# Power.net
KiCad netlist of a schematic drawn in Altium Designer
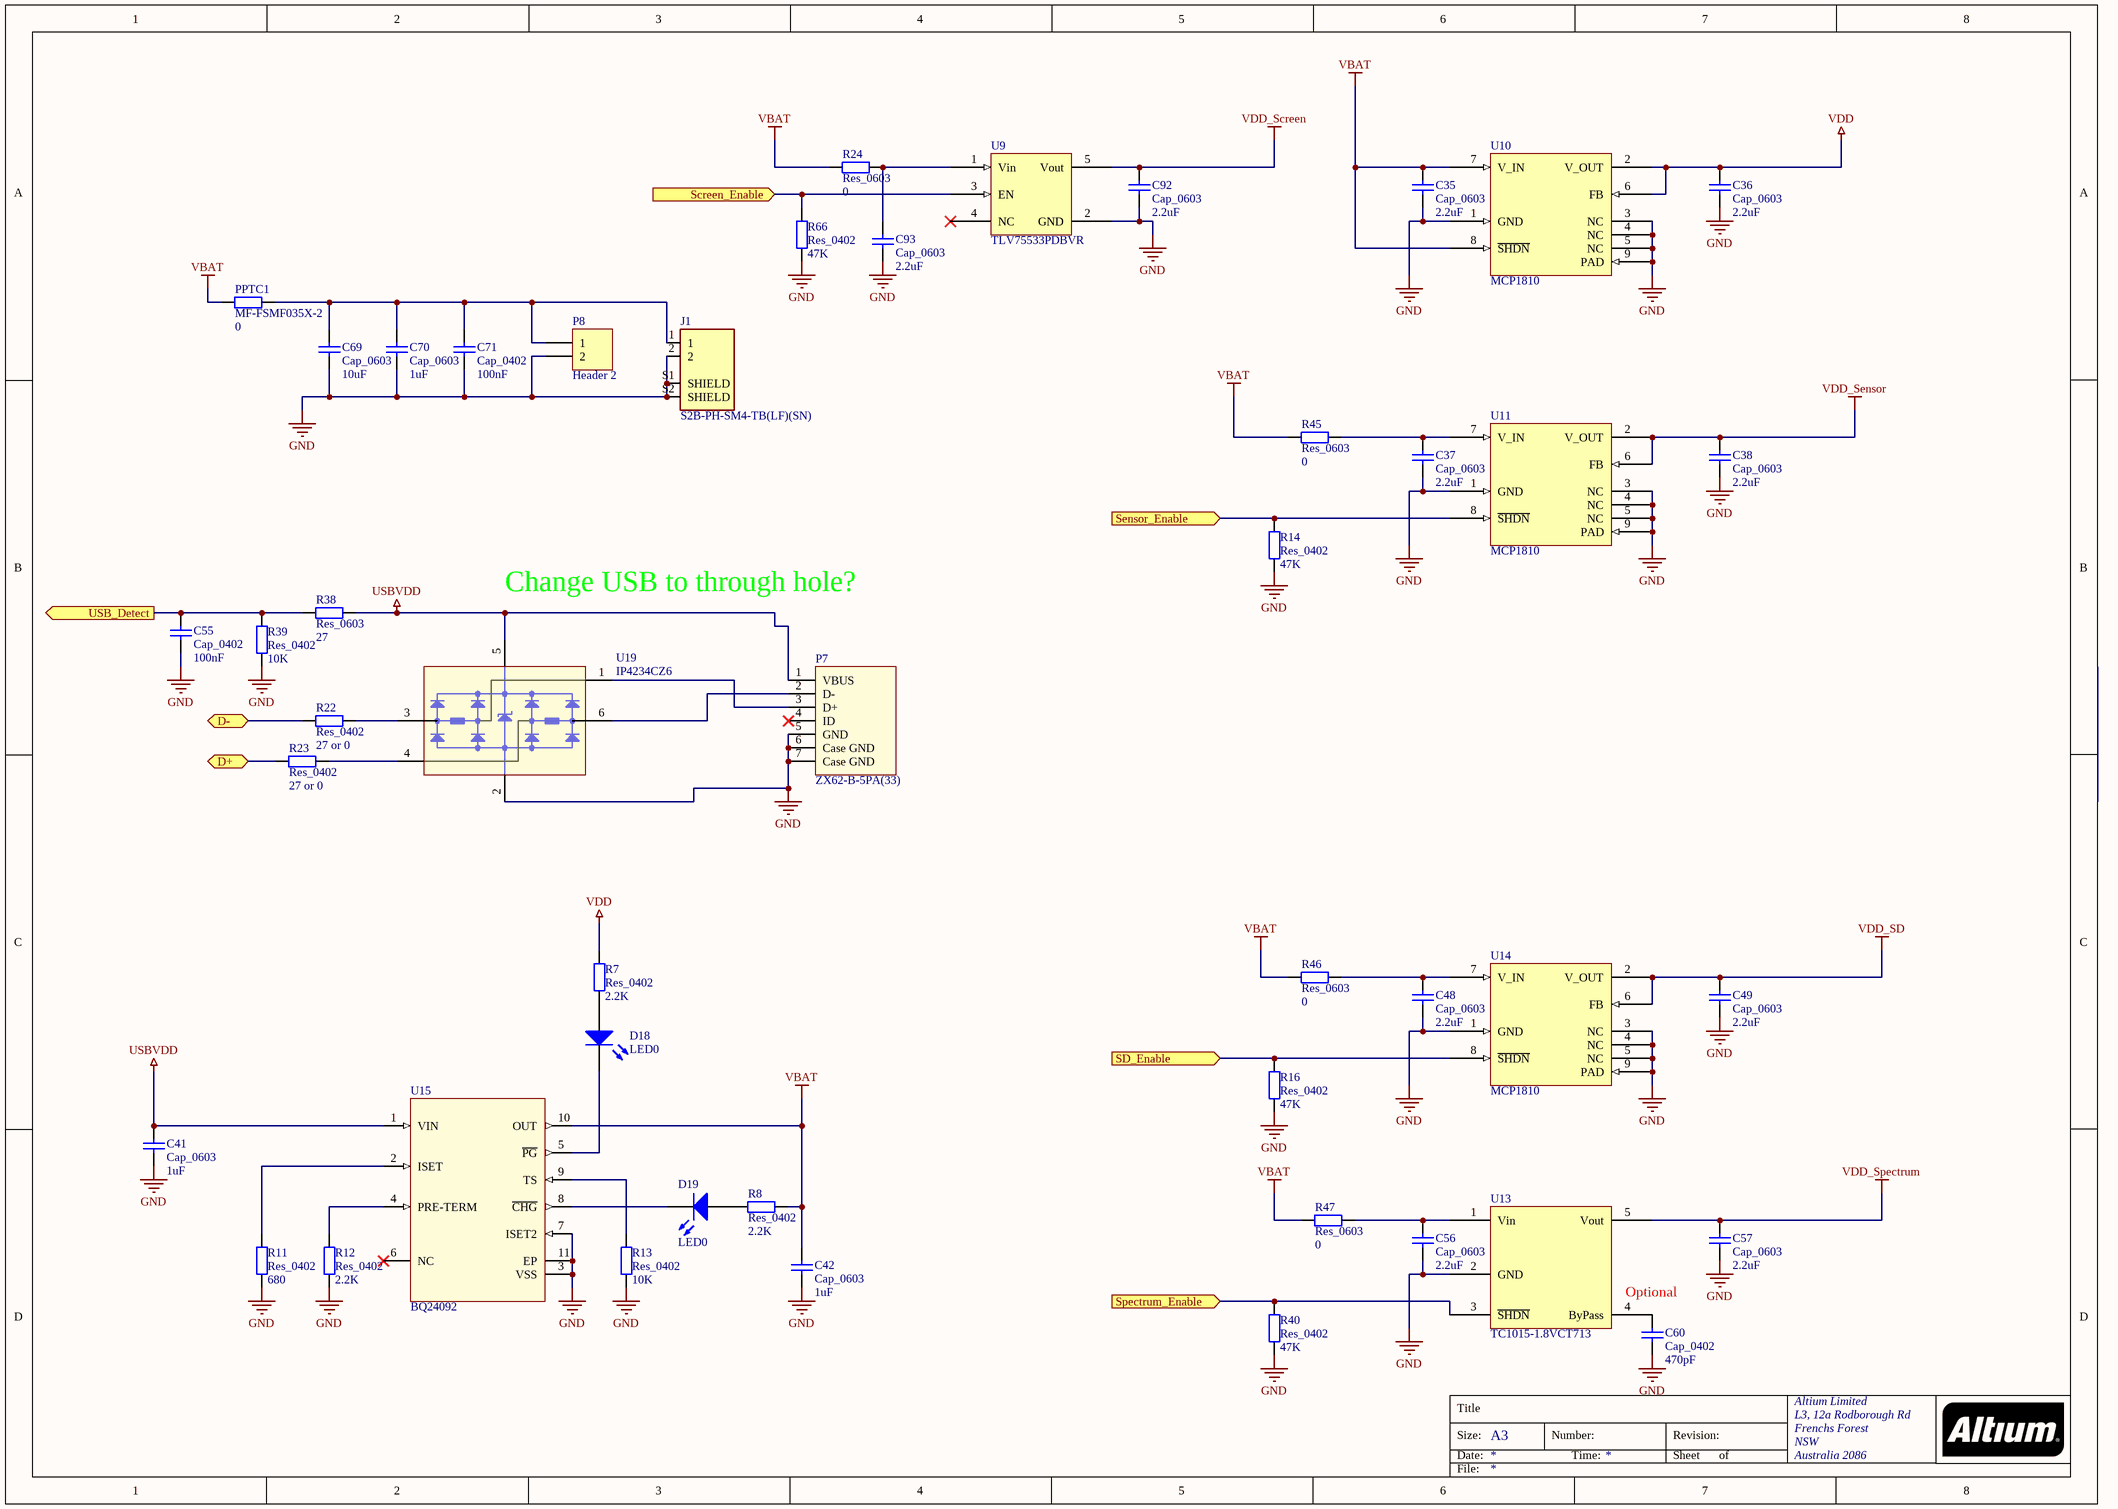
[diagram p0: Power.SchDoc]

(export (version "E")
  (design (tool "Eeschema 10.0.6"))
  (components
    (comp (ref "C35")
      (value "Cap_0603")
      (footprint "0603")
      (description "Capacitor")
      (fields (field (name "ALTIUM_VALUE") "2.2uF") (field (name "PUBLISHER") "Altium Limited"))
      (libsource (lib "Schematic_Components") (part "Cap_0603"))
    )
    (comp (ref "C36")
      (value "Cap_0603")
      (footprint "0603")
      (description "Capacitor")
      (fields (field (name "ALTIUM_VALUE") "2.2uF") (field (name "PUBLISHER") "Altium Limited"))
      (libsource (lib "Schematic_Components") (part "Cap_0603"))
    )
    (comp (ref "C37")
      (value "Cap_0603")
      (footprint "0603")
      (description "Capacitor")
      (fields (field (name "ALTIUM_VALUE") "2.2uF") (field (name "PUBLISHER") "Altium Limited"))
      (libsource (lib "Schematic_Components") (part "Cap_0603"))
    )
    (comp (ref "C38")
      (value "Cap_0603")
      (footprint "0603")
      (description "Capacitor")
      (fields (field (name "ALTIUM_VALUE") "2.2uF") (field (name "PUBLISHER") "Altium Limited"))
      (libsource (lib "Schematic_Components") (part "Cap_0603"))
    )
    (comp (ref "C41")
      (value "Cap_0603")
      (footprint "0603")
      (description "Capacitor")
      (fields (field (name "ALTIUM_VALUE") "1uF") (field (name "PUBLISHER") "Altium Limited"))
      (libsource (lib "Schematic_Components") (part "Cap_0603"))
    )
    (comp (ref "C42")
      (value "Cap_0603")
      (footprint "0603")
      (description "Capacitor")
      (fields (field (name "ALTIUM_VALUE") "1uF") (field (name "PUBLISHER") "Altium Limited"))
      (libsource (lib "Schematic_Components") (part "Cap_0603"))
    )
    (comp (ref "C48")
      (value "Cap_0603")
      (footprint "0603")
      (description "Capacitor")
      (fields (field (name "ALTIUM_VALUE") "2.2uF") (field (name "PUBLISHER") "Altium Limited"))
      (libsource (lib "Schematic_Components") (part "Cap_0603"))
    )
    (comp (ref "C49")
      (value "Cap_0603")
      (footprint "0603")
      (description "Capacitor")
      (fields (field (name "ALTIUM_VALUE") "2.2uF") (field (name "PUBLISHER") "Altium Limited"))
      (libsource (lib "Schematic_Components") (part "Cap_0603"))
    )
    (comp (ref "C55")
      (value "Cap_0402")
      (footprint "0402")
      (description "Capacitor")
      (fields (field (name "ALTIUM_VALUE") "100nF") (field (name "PUBLISHER") "Altium Limited"))
      (libsource (lib "Schematic_Components") (part "Cap_0402"))
    )
    (comp (ref "C56")
      (value "Cap_0603")
      (footprint "0603")
      (description "Capacitor")
      (fields (field (name "ALTIUM_VALUE") "2.2uF") (field (name "PUBLISHER") "Altium Limited"))
      (libsource (lib "Schematic_Components") (part "Cap_0603"))
    )
    (comp (ref "C57")
      (value "Cap_0603")
      (footprint "0603")
      (description "Capacitor")
      (fields (field (name "ALTIUM_VALUE") "2.2uF") (field (name "PUBLISHER") "Altium Limited"))
      (libsource (lib "Schematic_Components") (part "Cap_0603"))
    )
    (comp (ref "C60")
      (value "Cap_0402")
      (footprint "0402")
      (description "Capacitor")
      (fields (field (name "ALTIUM_VALUE") "470pF") (field (name "PUBLISHER") "Altium Limited"))
      (libsource (lib "Schematic_Components") (part "Cap_0402"))
    )
    (comp (ref "C69")
      (value "Cap_0603")
      (footprint "0603")
      (description "Capacitor")
      (fields (field (name "ALTIUM_VALUE") "10uF") (field (name "PUBLISHER") "Altium Limited"))
      (libsource (lib "Schematic_Components") (part "Cap_0603"))
    )
    (comp (ref "C70")
      (value "Cap_0603")
      (footprint "0603")
      (description "Capacitor")
      (fields (field (name "ALTIUM_VALUE") "1uF") (field (name "PUBLISHER") "Altium Limited"))
      (libsource (lib "Schematic_Components") (part "Cap_0603"))
    )
    (comp (ref "C71")
      (value "Cap_0402")
      (footprint "0402")
      (description "Capacitor")
      (fields (field (name "ALTIUM_VALUE") "100nF") (field (name "PUBLISHER") "Altium Limited"))
      (libsource (lib "Schematic_Components") (part "Cap_0402"))
    )
    (comp (ref "C92")
      (value "Cap_0603")
      (footprint "0603")
      (description "Capacitor")
      (fields (field (name "ALTIUM_VALUE") "2.2uF") (field (name "PUBLISHER") "Altium Limited"))
      (libsource (lib "Schematic_Components") (part "Cap_0603"))
    )
    (comp (ref "C93")
      (value "Cap_0603")
      (footprint "0603")
      (description "Capacitor")
      (fields (field (name "ALTIUM_VALUE") "2.2uF") (field (name "PUBLISHER") "Altium Limited"))
      (libsource (lib "Schematic_Components") (part "Cap_0603"))
    )
    (comp (ref "D18")
      (value "LED0")
      (footprint "0603")
      (description "Typical INFRARED GaAs LED")
      (fields (field (name "PUBLISHER") "Altium Limited"))
      (libsource (lib "Schematic_Components") (part "LED0"))
    )
    (comp (ref "D19")
      (value "LED0")
      (footprint "0603")
      (description "Typical INFRARED GaAs LED")
      (fields (field (name "PUBLISHER") "Altium Limited"))
      (libsource (lib "Schematic_Components") (part "LED0"))
    )
    (comp (ref "J1")
      (value "S2B-PH-SM4-TB(LF)(SN)")
      (footprint "JST_S2B-PH-SM4-TB(LF)(SN)")
      (description "PH Series 2 Position 2 mm Pitch Surface Mount Side Entry Shrouded Header")
      (fields (field (name "MF") "{'manufacturer': u'JST Sales'}"))
      (libsource (lib "Schematic_Components") (part "S2B-PH-SM4-TB(LF)(SN)"))
    )
    (comp (ref "P7")
      (value "ZX62-B-5PA(33)")
      (footprint "ZX62-B-5PA(33)")
      (description "USB Connector")
      (libsource (lib "Exeger_schematic_library") (part "ZX62-B-5PA(33)"))
    )
    (comp (ref "P8")
      (value "Header 2")
      (footprint "HDR1X2")
      (description "Header, 2-Pin")
      (fields (field (name "PUBLISHER") "Altium Limited"))
      (libsource (lib "Miscellaneous Connectors") (part "Header 2"))
    )
    (comp (ref "PPTC1")
      (value "MF-FSMF035X-2")
      (footprint "0603")
      (description "PPTC_0603")
      (fields (field (name "ALTIUM_VALUE") "0") (field (name "PUBLISHER") "Altium Limited"))
      (libsource (lib "Schematic_Components") (part "MF-FSMF035X-2"))
    )
    (comp (ref "R7")
      (value "Res_0402")
      (footprint "0402")
      (description "Resistor")
      (fields (field (name "ALTIUM_VALUE") "2.2K") (field (name "PUBLISHER") "Altium Limited"))
      (libsource (lib "Schematic_Components") (part "Res_0402"))
    )
    (comp (ref "R8")
      (value "Res_0402")
      (footprint "0402")
      (description "Resistor")
      (fields (field (name "ALTIUM_VALUE") "2.2K") (field (name "PUBLISHER") "Altium Limited"))
      (libsource (lib "") (part "Res_0402_1"))
    )
    (comp (ref "R11")
      (value "Res_0402")
      (footprint "0402")
      (description "Resistor")
      (fields (field (name "ALTIUM_VALUE") "680") (field (name "PUBLISHER") "Altium Limited"))
      (libsource (lib "Schematic_Components") (part "Res_0402"))
    )
    (comp (ref "R12")
      (value "Res_0402")
      (footprint "0402")
      (description "Resistor")
      (fields (field (name "ALTIUM_VALUE") "2.2K") (field (name "PUBLISHER") "Altium Limited"))
      (libsource (lib "Schematic_Components") (part "Res_0402"))
    )
    (comp (ref "R13")
      (value "Res_0402")
      (footprint "0402")
      (description "Resistor")
      (fields (field (name "ALTIUM_VALUE") "10K") (field (name "PUBLISHER") "Altium Limited"))
      (libsource (lib "Schematic_Components") (part "Res_0402"))
    )
    (comp (ref "R14")
      (value "Res_0402")
      (footprint "0402")
      (description "Resistor")
      (fields (field (name "ALTIUM_VALUE") "47K") (field (name "PUBLISHER") "Altium Limited"))
      (libsource (lib "") (part "Res_0402_2"))
    )
    (comp (ref "R16")
      (value "Res_0402")
      (footprint "0402")
      (description "Resistor")
      (fields (field (name "ALTIUM_VALUE") "47K") (field (name "PUBLISHER") "Altium Limited"))
      (libsource (lib "Schematic_Components") (part "Res_0402"))
    )
    (comp (ref "R22")
      (value "Res_0402")
      (footprint "0402")
      (description "Resistor")
      (fields (field (name "ALTIUM_VALUE") "27 or 0") (field (name "PUBLISHER") "Altium Limited"))
      (libsource (lib "") (part "Res_0402_3"))
    )
    (comp (ref "R23")
      (value "Res_0402")
      (footprint "0402")
      (description "Resistor")
      (fields (field (name "ALTIUM_VALUE") "27 or 0") (field (name "PUBLISHER") "Altium Limited"))
      (libsource (lib "") (part "Res_0402_3"))
    )
    (comp (ref "R24")
      (value "Res_0603")
      (footprint "0603")
      (description "Resistor")
      (fields (field (name "ALTIUM_VALUE") "0") (field (name "PUBLISHER") "Altium Limited"))
      (libsource (lib "Schematic_Components") (part "Res_0603"))
    )
    (comp (ref "R38")
      (value "Res_0603")
      (footprint "0603")
      (description "Resistor")
      (fields (field (name "ALTIUM_VALUE") "27") (field (name "PUBLISHER") "Altium Limited"))
      (libsource (lib "Schematic_Components") (part "Res_0603"))
    )
    (comp (ref "R39")
      (value "Res_0402")
      (footprint "0402")
      (description "Resistor")
      (fields (field (name "ALTIUM_VALUE") "10K") (field (name "PUBLISHER") "Altium Limited"))
      (libsource (lib "Schematic_Components") (part "Res_0402"))
    )
    (comp (ref "R40")
      (value "Res_0402")
      (footprint "0402")
      (description "Resistor")
      (fields (field (name "ALTIUM_VALUE") "47K") (field (name "PUBLISHER") "Altium Limited"))
      (libsource (lib "") (part "Res_0402_2"))
    )
    (comp (ref "R45")
      (value "Res_0603")
      (footprint "0603")
      (description "Resistor")
      (fields (field (name "ALTIUM_VALUE") "0") (field (name "PUBLISHER") "Altium Limited"))
      (libsource (lib "Schematic_Components") (part "Res_0603"))
    )
    (comp (ref "R46")
      (value "Res_0603")
      (footprint "0603")
      (description "Resistor")
      (fields (field (name "ALTIUM_VALUE") "0") (field (name "PUBLISHER") "Altium Limited"))
      (libsource (lib "Schematic_Components") (part "Res_0603"))
    )
    (comp (ref "R47")
      (value "Res_0603")
      (footprint "0603")
      (description "Resistor")
      (fields (field (name "ALTIUM_VALUE") "0") (field (name "PUBLISHER") "Altium Limited"))
      (libsource (lib "Schematic_Components") (part "Res_0603"))
    )
    (comp (ref "R66")
      (value "Res_0402")
      (footprint "0402")
      (description "Resistor")
      (fields (field (name "ALTIUM_VALUE") "47K") (field (name "PUBLISHER") "Altium Limited"))
      (libsource (lib "") (part "Res_0402_2"))
    )
    (comp (ref "U9")
      (value "TLV75533PDBVR")
      (footprint "SOT-23 (5)")
      (description "3.3V regulator")
      (libsource (lib "Schematic_Components") (part "TLV75533PDBVR"))
    )
    (comp (ref "U10")
      (value "MCP1810")
      (footprint "VDFN8")
      (description "3V Regulator, 150 mA")
      (libsource (lib "Schematic_Components") (part "MCP1810"))
    )
    (comp (ref "U11")
      (value "MCP1810")
      (footprint "VDFN8")
      (description "3V Regulator, 150 mA")
      (libsource (lib "Schematic_Components") (part "MCP1810"))
    )
    (comp (ref "U13")
      (value "TC1015-1.8VCT713")
      (footprint "SOT-23 (5)")
      (description "1.8V Regulator")
      (libsource (lib "Schematic_Components") (part "TC1015-1.8VCT713"))
    )
    (comp (ref "U14")
      (value "MCP1810")
      (footprint "VDFN8")
      (description "3V Regulator, 150 mA")
      (libsource (lib "Schematic_Components") (part "MCP1810"))
    )
    (comp (ref "U15")
      (value "BQ24092")
      (footprint "HVSSOP-10")
      (description "Battery Charger")
      (libsource (lib "Schematic_Components") (part "BQ24092"))
    )
    (comp (ref "U19")
      (value "IP4234CZ6")
      (footprint "TSOP95P280X110_HS-7N")
      (description "USB Line Protection")
      (libsource (lib "Exeger_schematic_library") (part "IP4234CZ6"))
    )
  )
  (nets
    (net (code "1") (name "/D+") (class "Default")
      (node (ref "R23") (pin "1") (pinfunction "1_1") (pintype "passive"))
    )
    (net (code "2") (name "/D-") (class "Default")
      (node (ref "R22") (pin "1") (pinfunction "1_1") (pintype "passive"))
    )
    (net (code "3") (name "/SD_Enable") (class "Default")
      (node (ref "R16") (pin "2") (pinfunction "2_2") (pintype "passive"))
      (node (ref "U14") (pin "8") (pinfunction "~{SHDN}_8") (pintype "input"))
    )
    (net (code "4") (name "/Screen_Enable") (class "Default")
      (node (ref "R66") (pin "1") (pinfunction "1_1") (pintype "passive"))
      (node (ref "U9") (pin "3") (pinfunction "EN_3") (pintype "input"))
    )
    (net (code "5") (name "/Sensor_Enable") (class "Default")
      (node (ref "R14") (pin "1") (pinfunction "1_1") (pintype "passive"))
      (node (ref "U11") (pin "8") (pinfunction "~{SHDN}_8") (pintype "input"))
    )
    (net (code "6") (name "/Spectrum_Enable") (class "Default")
      (node (ref "R40") (pin "1") (pinfunction "1_1") (pintype "passive"))
      (node (ref "U13") (pin "3") (pinfunction "~{SHDN}_3") (pintype "passive"))
    )
    (net (code "7") (name "/USB_Detect") (class "Default")
      (node (ref "C55") (pin "2") (pinfunction "2_2") (pintype "passive"))
      (node (ref "R38") (pin "1") (pinfunction "1_1") (pintype "passive"))
      (node (ref "R39") (pin "2") (pinfunction "2_2") (pintype "passive"))
    )
    (net (code "8") (name "GND") (class "Default")
      (node (ref "C35") (pin "1") (pinfunction "1_1") (pintype "passive"))
      (node (ref "C36") (pin "1") (pinfunction "1_1") (pintype "passive"))
      (node (ref "C37") (pin "1") (pinfunction "1_1") (pintype "passive"))
      (node (ref "C38") (pin "1") (pinfunction "1_1") (pintype "passive"))
      (node (ref "C41") (pin "1") (pinfunction "1_1") (pintype "passive"))
      (node (ref "C42") (pin "1") (pinfunction "1_1") (pintype "passive"))
      (node (ref "C48") (pin "1") (pinfunction "1_1") (pintype "passive"))
      (node (ref "C49") (pin "1") (pinfunction "1_1") (pintype "passive"))
      (node (ref "C55") (pin "1") (pinfunction "1_1") (pintype "passive"))
      (node (ref "C56") (pin "1") (pinfunction "1_1") (pintype "passive"))
      (node (ref "C57") (pin "1") (pinfunction "1_1") (pintype "passive"))
      (node (ref "C60") (pin "1") (pinfunction "1_1") (pintype "passive"))
      (node (ref "C69") (pin "1") (pinfunction "1_1") (pintype "passive"))
      (node (ref "C70") (pin "1") (pinfunction "1_1") (pintype "passive"))
      (node (ref "C71") (pin "1") (pinfunction "1_1") (pintype "passive"))
      (node (ref "C92") (pin "1") (pinfunction "1_1") (pintype "passive"))
      (node (ref "C93") (pin "1") (pinfunction "1_1") (pintype "passive"))
      (node (ref "J1") (pin "2") (pinfunction "2_2") (pintype "passive"))
      (node (ref "J1") (pin "S1") (pinfunction "SHIELD_S1") (pintype "passive"))
      (node (ref "J1") (pin "S2") (pinfunction "SHIELD_S2") (pintype "passive"))
      (node (ref "P7") (pin "5") (pinfunction "GND_5") (pintype "power_in"))
      (node (ref "P7") (pin "6") (pinfunction "Case_GND_6") (pintype "power_in"))
      (node (ref "P7") (pin "7") (pinfunction "Case_GND_7") (pintype "passive"))
      (node (ref "P8") (pin "2") (pinfunction "2_2") (pintype "passive"))
      (node (ref "R11") (pin "1") (pinfunction "1_1") (pintype "passive"))
      (node (ref "R12") (pin "1") (pinfunction "1_1") (pintype "passive"))
      (node (ref "R13") (pin "1") (pinfunction "1_1") (pintype "passive"))
      (node (ref "R14") (pin "2") (pinfunction "2_2") (pintype "passive"))
      (node (ref "R16") (pin "1") (pinfunction "1_1") (pintype "passive"))
      (node (ref "R39") (pin "1") (pinfunction "1_1") (pintype "passive"))
      (node (ref "R40") (pin "2") (pinfunction "2_2") (pintype "passive"))
      (node (ref "R66") (pin "2") (pinfunction "2_2") (pintype "passive"))
      (node (ref "U10") (pin "1") (pinfunction "GND_1") (pintype "input"))
      (node (ref "U10") (pin "3") (pinfunction "NC_3") (pintype "passive"))
      (node (ref "U10") (pin "4") (pinfunction "NC_4") (pintype "passive"))
      (node (ref "U10") (pin "5") (pinfunction "NC_5") (pintype "passive"))
      (node (ref "U10") (pin "9") (pinfunction "PAD_9") (pintype "input"))
      (node (ref "U11") (pin "1") (pinfunction "GND_1") (pintype "input"))
      (node (ref "U11") (pin "3") (pinfunction "NC_3") (pintype "passive"))
      (node (ref "U11") (pin "4") (pinfunction "NC_4") (pintype "passive"))
      (node (ref "U11") (pin "5") (pinfunction "NC_5") (pintype "passive"))
      (node (ref "U11") (pin "9") (pinfunction "PAD_9") (pintype "input"))
      (node (ref "U13") (pin "2") (pinfunction "GND_2") (pintype "passive"))
      (node (ref "U14") (pin "1") (pinfunction "GND_1") (pintype "input"))
      (node (ref "U14") (pin "3") (pinfunction "NC_3") (pintype "passive"))
      (node (ref "U14") (pin "4") (pinfunction "NC_4") (pintype "passive"))
      (node (ref "U14") (pin "5") (pinfunction "NC_5") (pintype "passive"))
      (node (ref "U14") (pin "9") (pinfunction "PAD_9") (pintype "input"))
      (node (ref "U15") (pin "11") (pinfunction "EP_11") (pintype "power_in"))
      (node (ref "U15") (pin "3") (pinfunction "VSS_3") (pintype "power_in"))
      (node (ref "U15") (pin "7") (pinfunction "ISET2_7") (pintype "input"))
      (node (ref "U19") (pin "2") (pinfunction "GND_2") (pintype "power_in"))
      (node (ref "U9") (pin "2") (pinfunction "GND_2") (pintype "passive"))
    )
    (net (code "9") (name "Net-(C69-Pad2)") (class "Default")
      (node (ref "C69") (pin "2") (pinfunction "2_2") (pintype "passive"))
      (node (ref "C70") (pin "2") (pinfunction "2_2") (pintype "passive"))
      (node (ref "C71") (pin "2") (pinfunction "2_2") (pintype "passive"))
      (node (ref "J1") (pin "1") (pinfunction "1_1") (pintype "passive"))
      (node (ref "P8") (pin "1") (pinfunction "1_1") (pintype "passive"))
      (node (ref "PPTC1") (pin "2") (pinfunction "2_2") (pintype "passive"))
    )
    (net (code "10") (name "Net-(D18-A)") (class "Default")
      (node (ref "D18") (pin "2") (pinfunction "A_2") (pintype "passive"))
      (node (ref "R7") (pin "1") (pinfunction "1_1") (pintype "passive"))
    )
    (net (code "11") (name "Net-(D18-K)") (class "Default")
      (node (ref "D18") (pin "1") (pinfunction "K_1") (pintype "passive"))
      (node (ref "U15") (pin "5") (pinfunction "~{PG}_5") (pintype "output"))
    )
    (net (code "12") (name "Net-(D19-A)") (class "Default")
      (node (ref "D19") (pin "2") (pinfunction "A_2") (pintype "passive"))
      (node (ref "R8") (pin "2") (pinfunction "2_2") (pintype "passive"))
    )
    (net (code "13") (name "Net-(D19-K)") (class "Default")
      (node (ref "D19") (pin "1") (pinfunction "K_1") (pintype "passive"))
      (node (ref "U15") (pin "8") (pinfunction "~{CHG}_8") (pintype "output"))
    )
    (net (code "14") (name "Net-(P7-D+)") (class "Default")
      (node (ref "P7") (pin "3") (pinfunction "D+_3") (pintype "passive"))
      (node (ref "U19") (pin "1") (pinfunction "CH1_A_1") (pintype "passive"))
    )
    (net (code "15") (name "Net-(P7-D-)") (class "Default")
      (node (ref "P7") (pin "2") (pinfunction "D-_2") (pintype "passive"))
      (node (ref "U19") (pin "6") (pinfunction "CH2_B_6") (pintype "passive"))
    )
    (net (code "16") (name "Net-(U9-Vin)") (class "Default")
      (node (ref "C93") (pin "2") (pinfunction "2_2") (pintype "passive"))
      (node (ref "R24") (pin "2") (pinfunction "2_2") (pintype "passive"))
      (node (ref "U9") (pin "1") (pinfunction "Vin_1") (pintype "input"))
    )
    (net (code "17") (name "Net-(U11-V_IN)") (class "Default")
      (node (ref "C37") (pin "2") (pinfunction "2_2") (pintype "passive"))
      (node (ref "R45") (pin "2") (pinfunction "2_2") (pintype "passive"))
      (node (ref "U11") (pin "7") (pinfunction "V_IN_7") (pintype "input"))
    )
    (net (code "18") (name "Net-(U13-ByPass)") (class "Default")
      (node (ref "C60") (pin "2") (pinfunction "2_2") (pintype "passive"))
      (node (ref "U13") (pin "4") (pinfunction "ByPass_4") (pintype "passive"))
    )
    (net (code "19") (name "Net-(U13-Vin)") (class "Default")
      (node (ref "C56") (pin "2") (pinfunction "2_2") (pintype "passive"))
      (node (ref "R47") (pin "2") (pinfunction "2_2") (pintype "passive"))
      (node (ref "U13") (pin "1") (pinfunction "Vin_1") (pintype "passive"))
    )
    (net (code "20") (name "Net-(U14-V_IN)") (class "Default")
      (node (ref "C48") (pin "2") (pinfunction "2_2") (pintype "passive"))
      (node (ref "R46") (pin "2") (pinfunction "2_2") (pintype "passive"))
      (node (ref "U14") (pin "7") (pinfunction "V_IN_7") (pintype "input"))
    )
    (net (code "21") (name "Net-(U15-ISET)") (class "Default")
      (node (ref "R11") (pin "2") (pinfunction "2_2") (pintype "passive"))
      (node (ref "U15") (pin "2") (pinfunction "ISET_2") (pintype "input"))
    )
    (net (code "22") (name "Net-(U15-PRE-TERM)") (class "Default")
      (node (ref "R12") (pin "2") (pinfunction "2_2") (pintype "passive"))
      (node (ref "U15") (pin "4") (pinfunction "PRE-TERM_4") (pintype "input"))
    )
    (net (code "23") (name "Net-(U15-TS)") (class "Default")
      (node (ref "R13") (pin "2") (pinfunction "2_2") (pintype "passive"))
      (node (ref "U15") (pin "9") (pinfunction "TS_9") (pintype "input"))
    )
    (net (code "24") (name "Net-(U19-CH1_B)") (class "Default")
      (node (ref "R22") (pin "2") (pinfunction "2_2") (pintype "passive"))
      (node (ref "U19") (pin "3") (pinfunction "CH1_B_3") (pintype "passive"))
    )
    (net (code "25") (name "Net-(U19-CH2_A)") (class "Default")
      (node (ref "R23") (pin "2") (pinfunction "2_2") (pintype "passive"))
      (node (ref "U19") (pin "4") (pinfunction "CH2_A_4") (pintype "passive"))
    )
    (net (code "26") (name "USBVDD") (class "Default")
      (node (ref "C41") (pin "2") (pinfunction "2_2") (pintype "passive"))
      (node (ref "P7") (pin "1") (pinfunction "VBUS_1") (pintype "power_in"))
      (node (ref "R38") (pin "2") (pinfunction "2_2") (pintype "passive"))
      (node (ref "U15") (pin "1") (pinfunction "VIN_1") (pintype "input"))
      (node (ref "U19") (pin "5") (pinfunction "VCC_5") (pintype "power_in"))
    )
    (net (code "27") (name "VBAT") (class "Default")
      (node (ref "C35") (pin "2") (pinfunction "2_2") (pintype "passive"))
      (node (ref "C42") (pin "2") (pinfunction "2_2") (pintype "passive"))
      (node (ref "PPTC1") (pin "1") (pinfunction "1_1") (pintype "passive"))
      (node (ref "R24") (pin "1") (pinfunction "1_1") (pintype "passive"))
      (node (ref "R45") (pin "1") (pinfunction "1_1") (pintype "passive"))
      (node (ref "R46") (pin "1") (pinfunction "1_1") (pintype "passive"))
      (node (ref "R47") (pin "1") (pinfunction "1_1") (pintype "passive"))
      (node (ref "R8") (pin "1") (pinfunction "1_1") (pintype "passive"))
      (node (ref "U10") (pin "7") (pinfunction "V_IN_7") (pintype "input"))
      (node (ref "U10") (pin "8") (pinfunction "~{SHDN}_8") (pintype "input"))
      (node (ref "U15") (pin "10") (pinfunction "OUT_10") (pintype "output"))
    )
    (net (code "28") (name "VDD") (class "Default")
      (node (ref "C36") (pin "2") (pinfunction "2_2") (pintype "passive"))
      (node (ref "R7") (pin "2") (pinfunction "2_2") (pintype "passive"))
      (node (ref "U10") (pin "2") (pinfunction "V_OUT_2") (pintype "passive"))
      (node (ref "U10") (pin "6") (pinfunction "FB_6") (pintype "input"))
    )
    (net (code "29") (name "VDD_SD") (class "Default")
      (node (ref "C49") (pin "2") (pinfunction "2_2") (pintype "passive"))
      (node (ref "U14") (pin "2") (pinfunction "V_OUT_2") (pintype "passive"))
      (node (ref "U14") (pin "6") (pinfunction "FB_6") (pintype "input"))
    )
    (net (code "30") (name "VDD_Screen") (class "Default")
      (node (ref "C92") (pin "2") (pinfunction "2_2") (pintype "passive"))
      (node (ref "U9") (pin "5") (pinfunction "Vout_5") (pintype "passive"))
    )
    (net (code "31") (name "VDD_Sensor") (class "Default")
      (node (ref "C38") (pin "2") (pinfunction "2_2") (pintype "passive"))
      (node (ref "U11") (pin "2") (pinfunction "V_OUT_2") (pintype "passive"))
      (node (ref "U11") (pin "6") (pinfunction "FB_6") (pintype "input"))
    )
    (net (code "32") (name "VDD_Spectrum") (class "Default")
      (node (ref "C57") (pin "2") (pinfunction "2_2") (pintype "passive"))
      (node (ref "U13") (pin "5") (pinfunction "Vout_5") (pintype "passive"))
    )
    (net (code "33") (name "unconnected-(P7-ID-Pad4)") (class "Default")
      (node (ref "P7") (pin "4") (pinfunction "ID_4") (pintype "passive+no_connect"))
    )
    (net (code "34") (name "unconnected-(U9-NC-Pad4)") (class "Default")
      (node (ref "U9") (pin "4") (pinfunction "NC_4") (pintype "passive+no_connect"))
    )
    (net (code "35") (name "unconnected-(U15-NC-Pad6)") (class "Default")
      (node (ref "U15") (pin "6") (pinfunction "NC_6") (pintype "passive+no_connect"))
    )
  )
)
